# Real_time_Clock_Circuit.net
KiCad netlist of a schematic drawn in EAGLE
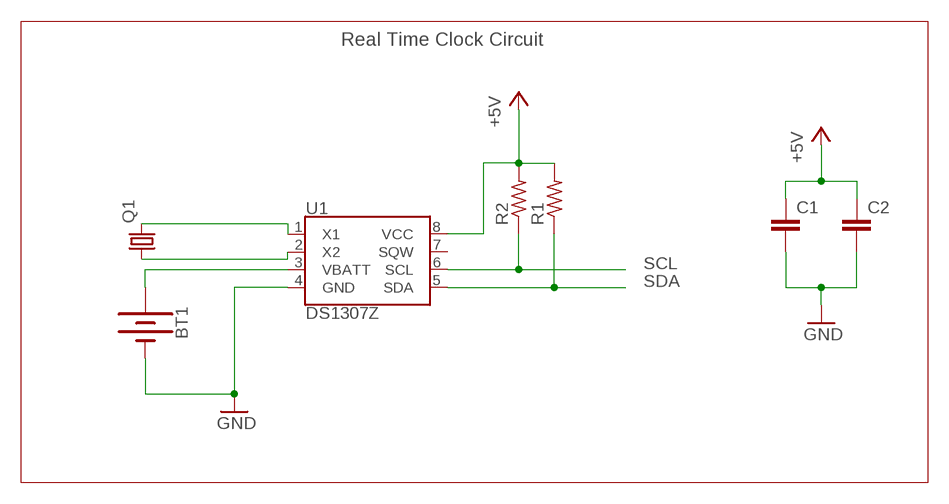
[diagram p0: schematic, sheet 1]

(export (version "E")
  (design (tool "Eeschema 10.0.6"))
  (components
    (comp (ref "BT1")
      (value "BATTERY-20MM_PTH")
      (footprint "eagle-import:BATTCOM_20MM_PTH")
      (libsource (lib "eagle-import") (part "BATTERY-20MM_PTH"))
    )
    (comp (ref "C1")
      (value "C-EUC0805")
      (footprint "eagle-import:C0805")
      (libsource (lib "eagle-import") (part "C-EUC0805"))
    )
    (comp (ref "C2")
      (value "C-EUC0805")
      (footprint "eagle-import:C0805")
      (libsource (lib "eagle-import") (part "C-EUC0805"))
    )
    (comp (ref "Q1")
      (value "CRYSTALMM39SL")
      (footprint "eagle-import:MM39SL")
      (libsource (lib "eagle-import") (part "CRYSTALMM39SL"))
    )
    (comp (ref "R1")
      (value "R-US_R0805")
      (footprint "eagle-import:R0805")
      (libsource (lib "eagle-import") (part "R-US_R0805"))
    )
    (comp (ref "R2")
      (value "R-US_R0805")
      (footprint "eagle-import:R0805")
      (libsource (lib "eagle-import") (part "R-US_R0805"))
    )
    (comp (ref "U1")
      (value "DS1307Z")
      (footprint "eagle-import:SO08-0.15")
      (libsource (lib "eagle-import") (part "DS1307Z"))
    )
  )
  (nets
    (net (code "1") (name "+5V") (class "Default")
      (node (ref "C1") (pin "1") (pinfunction "1_1") (pintype "passive"))
      (node (ref "C2") (pin "1") (pinfunction "1_1") (pintype "passive"))
      (node (ref "R1") (pin "2") (pinfunction "2_2") (pintype "passive"))
      (node (ref "R2") (pin "2") (pinfunction "2_2") (pintype "passive"))
      (node (ref "U1") (pin "8") (pinfunction "VCC_8") (pintype "bidirectional"))
    )
    (net (code "2") (name "/SCL") (class "Default")
      (node (ref "R2") (pin "1") (pinfunction "1_1") (pintype "passive"))
      (node (ref "U1") (pin "6") (pinfunction "SCL_6") (pintype "bidirectional"))
    )
    (net (code "3") (name "/SDA") (class "Default")
      (node (ref "R1") (pin "1") (pinfunction "1_1") (pintype "passive"))
      (node (ref "U1") (pin "5") (pinfunction "SDA_5") (pintype "bidirectional"))
    )
    (net (code "4") (name "GND") (class "Default")
      (node (ref "BT1") (pin "2") (pinfunction "-_2") (pintype "power_in"))
      (node (ref "C1") (pin "2") (pinfunction "2_2") (pintype "passive"))
      (node (ref "C2") (pin "2") (pinfunction "2_2") (pintype "passive"))
      (node (ref "U1") (pin "4") (pinfunction "GND_4") (pintype "bidirectional"))
    )
    (net (code "5") (name "Net-(BT1-+)") (class "Default")
      (node (ref "BT1") (pin "1") (pinfunction "+_1") (pintype "power_in"))
      (node (ref "U1") (pin "3") (pinfunction "VBATT_3") (pintype "bidirectional"))
    )
    (net (code "6") (name "Net-(Q1-2)") (class "Default")
      (node (ref "Q1") (pin "4") (pinfunction "2_4") (pintype "passive"))
      (node (ref "U1") (pin "1") (pinfunction "X1_1") (pintype "bidirectional"))
    )
    (net (code "7") (name "Net-(U1-X2)") (class "Default")
      (node (ref "Q1") (pin "1") (pinfunction "1_1") (pintype "passive"))
      (node (ref "U1") (pin "2") (pinfunction "X2_2") (pintype "bidirectional"))
    )
    (net (code "8") (name "unconnected-(U1-SQW-Pad7)") (class "Default")
      (node (ref "U1") (pin "7") (pinfunction "SQW_7") (pintype "bidirectional"))
    )
  )
)
